# dcdc_converter.net
KiCad netlist of a schematic drawn in Altium Designer
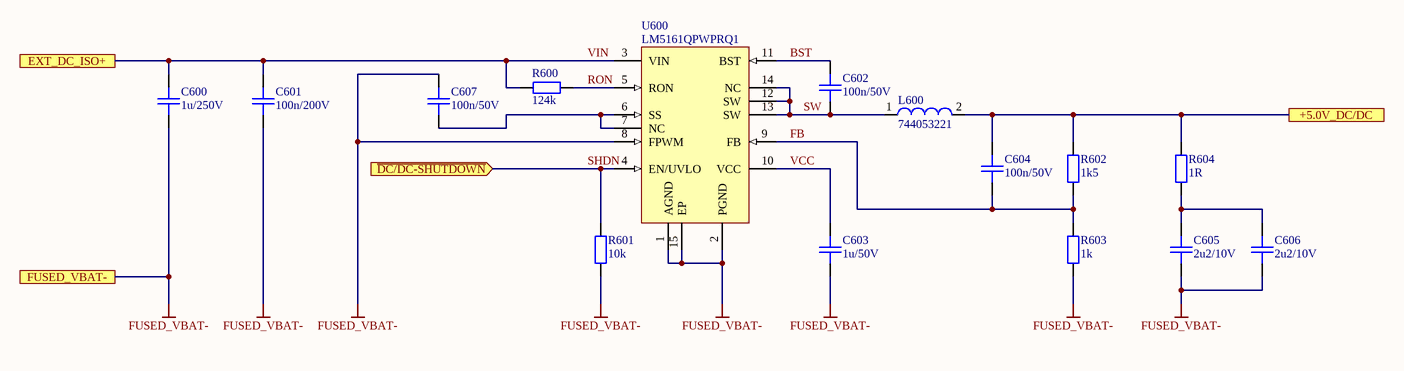
[diagram p0: dcdc_converter.SchDoc]

(export (version "E")
  (design (tool "Eeschema 10.0.6"))
  (components
    (comp (ref "C600")
      (value "1u/250V")
      (footprint "CAPC4532X16N")
      (description "MLCC")
      (fields (field (name "PART NUMBER") "gen_C_ceramic_1u_250V_X7R_1812"))
      (libsource (lib "OE750") (part "C"))
    )
    (comp (ref "C601")
      (value "100n/200V")
      (footprint "CAPC3216X18N")
      (description "MLCC")
      (fields (field (name "PART NUMBER") "gen_C_ceramic_100n_200V_X7R_1206"))
      (libsource (lib "OE750") (part "C"))
    )
    (comp (ref "C602")
      (value "100n/50V")
      (footprint "CAPC1608X08N")
      (description "MLCC")
      (fields (field (name "PART NUMBER") "gen_C_ceramic_100n_50V_X7R_0603"))
      (libsource (lib "OE750") (part "C"))
    )
    (comp (ref "C603")
      (value "1u/50V")
      (footprint "CAPC2012X14N")
      (description "MLCC")
      (fields (field (name "PART NUMBER") "gen_C_ceramic_1u_50V_X7R_0805") (field (name "TOLERANCE") "± 10%"))
      (libsource (lib "OE750") (part "C"))
    )
    (comp (ref "C604")
      (value "100n/50V")
      (footprint "CAPC1608X08N")
      (description "MLCC")
      (fields (field (name "PART NUMBER") "gen_C_ceramic_100n_50V_X7R_0603"))
      (libsource (lib "OE750") (part "C"))
    )
    (comp (ref "C605")
      (value "2u2/10V")
      (footprint "CAPC2012X14N")
      (description "MLCC")
      (fields (field (name "PART NUMBER") "gen_C_ceramic_2u2_10V_X7R_0805"))
      (libsource (lib "OE750") (part "C"))
    )
    (comp (ref "C606")
      (value "2u2/10V")
      (footprint "CAPC2012X14N")
      (description "MLCC")
      (fields (field (name "PART NUMBER") "gen_C_ceramic_2u2_10V_X7R_0805"))
      (libsource (lib "OE750") (part "C"))
    )
    (comp (ref "C607")
      (value "100n/50V")
      (footprint "CAPC1608X08N")
      (description "MLCC")
      (fields (field (name "PART NUMBER") "gen_C_ceramic_100n_50V_X7R_0603"))
      (libsource (lib "OE750") (part "C"))
    )
    (comp (ref "L600")
      (value "744053221")
      (footprint "WE-TPC-5828-LH")
      (description "SMD Shielded Tiny Power Inductor WE-TPC, L = 220 µH")
      (libsource (lib "Altium Content Vault") (part "PAS-IND-INDUCTOR-2"))
    )
    (comp (ref "R600")
      (value "124k")
      (footprint "RESC1608X05N")
      (description "SMD Resistor 124k 0603")
      (fields (field (name "PART NUMBER") "gen_R_124k_0603") (field (name "TOLERANCE") "1%"))
      (libsource (lib "OE750") (part "R"))
    )
    (comp (ref "R601")
      (value "10k")
      (footprint "RESC1608X05N")
      (description "SMD Resistor 10k 0603")
      (fields (field (name "PART NUMBER") "gen_R_10k_0603") (field (name "TOLERANCE") "1%"))
      (libsource (lib "OE750") (part "R"))
    )
    (comp (ref "R602")
      (value "1k5")
      (footprint "RESC1608X05N")
      (description "SMD Resistor 1k5 0603")
      (fields (field (name "PART NUMBER") "gen_R_1k5_0603") (field (name "TOLERANCE") "1%"))
      (libsource (lib "OE750") (part "R"))
    )
    (comp (ref "R603")
      (value "1k")
      (footprint "RESC1608X05N")
      (description "SMD Resistor 1k 0603")
      (fields (field (name "PART NUMBER") "gen_R_1k_0603") (field (name "TOLERANCE") "1%"))
      (libsource (lib "OE750") (part "R"))
    )
    (comp (ref "R604")
      (value "1R")
      (footprint "RESC2012X05N")
      (description "SMD Resistor 1R 0805")
      (fields (field (name "PART NUMBER") "gen_R_1R_0805") (field (name "TOLERANCE") "1%"))
      (libsource (lib "OE750") (part "R"))
    )
    (comp (ref "U600")
      (value "LM5161QPWPRQ1")
      (footprint "PWP0014A")
      (description "Automotive DC/DC buck converter")
      (fields (field (name "MANUFACTURER") "Texas Instruments"))
      (libsource (lib "OE750") (part "LM5161QPWPRQ1"))
    )
  )
  (nets
    (net (code "1") (name "/+5.0V_DC{slash}DC") (class "Default")
      (node (ref "C604") (pin "2") (pinfunction "2_2") (pintype "passive"))
      (node (ref "L600") (pin "2") (pinfunction "2_2") (pintype "passive"))
      (node (ref "R602") (pin "1") (pinfunction "1_1") (pintype "passive"))
      (node (ref "R604") (pin "1") (pinfunction "1_1") (pintype "passive"))
    )
    (net (code "2") (name "/BST") (class "Default")
      (node (ref "C602") (pin "2") (pinfunction "2_2") (pintype "passive"))
      (node (ref "U600") (pin "11") (pinfunction "BST_11") (pintype "input"))
    )
    (net (code "3") (name "/FB") (class "Default")
      (node (ref "C604") (pin "1") (pinfunction "1_1") (pintype "passive"))
      (node (ref "R602") (pin "2") (pinfunction "2_2") (pintype "passive"))
      (node (ref "R603") (pin "1") (pinfunction "1_1") (pintype "passive"))
      (node (ref "U600") (pin "9") (pinfunction "FB_9") (pintype "input"))
    )
    (net (code "4") (name "/RON") (class "Default")
      (node (ref "R600") (pin "1") (pinfunction "1_1") (pintype "passive"))
      (node (ref "U600") (pin "5") (pinfunction "RON_5") (pintype "input"))
    )
    (net (code "5") (name "/SHDN") (class "Default")
      (node (ref "R601") (pin "1") (pinfunction "1_1") (pintype "passive"))
      (node (ref "U600") (pin "4") (pinfunction "EN/UVLO_4") (pintype "input"))
    )
    (net (code "6") (name "/SW") (class "Default")
      (node (ref "C602") (pin "1") (pinfunction "1_1") (pintype "passive"))
      (node (ref "L600") (pin "1") (pinfunction "1_1") (pintype "passive"))
      (node (ref "U600") (pin "12") (pinfunction "SW_12") (pintype "power_in"))
      (node (ref "U600") (pin "13") (pinfunction "SW_13") (pintype "power_in"))
      (node (ref "U600") (pin "14") (pinfunction "NC_14") (pintype "passive"))
    )
    (net (code "7") (name "/VCC") (class "Default")
      (node (ref "C603") (pin "2") (pinfunction "2_2") (pintype "passive"))
      (node (ref "U600") (pin "10") (pinfunction "VCC_10") (pintype "power_in"))
    )
    (net (code "8") (name "/VIN") (class "Default")
      (node (ref "C600") (pin "2") (pinfunction "2_2") (pintype "passive"))
      (node (ref "C601") (pin "2") (pinfunction "2_2") (pintype "passive"))
      (node (ref "R600") (pin "2") (pinfunction "2_2") (pintype "passive"))
      (node (ref "U600") (pin "3") (pinfunction "VIN_3") (pintype "power_in"))
    )
    (net (code "9") (name "FUSED_VBAT-") (class "Default")
      (node (ref "C600") (pin "1") (pinfunction "1_1") (pintype "passive"))
      (node (ref "C601") (pin "1") (pinfunction "1_1") (pintype "passive"))
      (node (ref "C603") (pin "1") (pinfunction "1_1") (pintype "passive"))
      (node (ref "C605") (pin "1") (pinfunction "1_1") (pintype "passive"))
      (node (ref "C606") (pin "1") (pinfunction "1_1") (pintype "passive"))
      (node (ref "C607") (pin "2") (pinfunction "2_2") (pintype "passive"))
      (node (ref "R601") (pin "2") (pinfunction "2_2") (pintype "passive"))
      (node (ref "R603") (pin "2") (pinfunction "2_2") (pintype "passive"))
      (node (ref "U600") (pin "1") (pinfunction "AGND_1") (pintype "power_in"))
      (node (ref "U600") (pin "15") (pinfunction "EP_15") (pintype "power_in"))
      (node (ref "U600") (pin "2") (pinfunction "PGND_2") (pintype "power_in"))
      (node (ref "U600") (pin "8") (pinfunction "FPWM_8") (pintype "input"))
    )
    (net (code "10") (name "Net-(C605-Pad2)") (class "Default")
      (node (ref "C605") (pin "2") (pinfunction "2_2") (pintype "passive"))
      (node (ref "C606") (pin "2") (pinfunction "2_2") (pintype "passive"))
      (node (ref "R604") (pin "2") (pinfunction "2_2") (pintype "passive"))
    )
    (net (code "11") (name "Net-(U600-SS)") (class "Default")
      (node (ref "C607") (pin "1") (pinfunction "1_1") (pintype "passive"))
      (node (ref "U600") (pin "6") (pinfunction "SS_6") (pintype "input"))
      (node (ref "U600") (pin "7") (pinfunction "NC_7") (pintype "passive"))
    )
  )
)
